# Sensors.net
KiCad netlist of a schematic drawn in Altium Designer
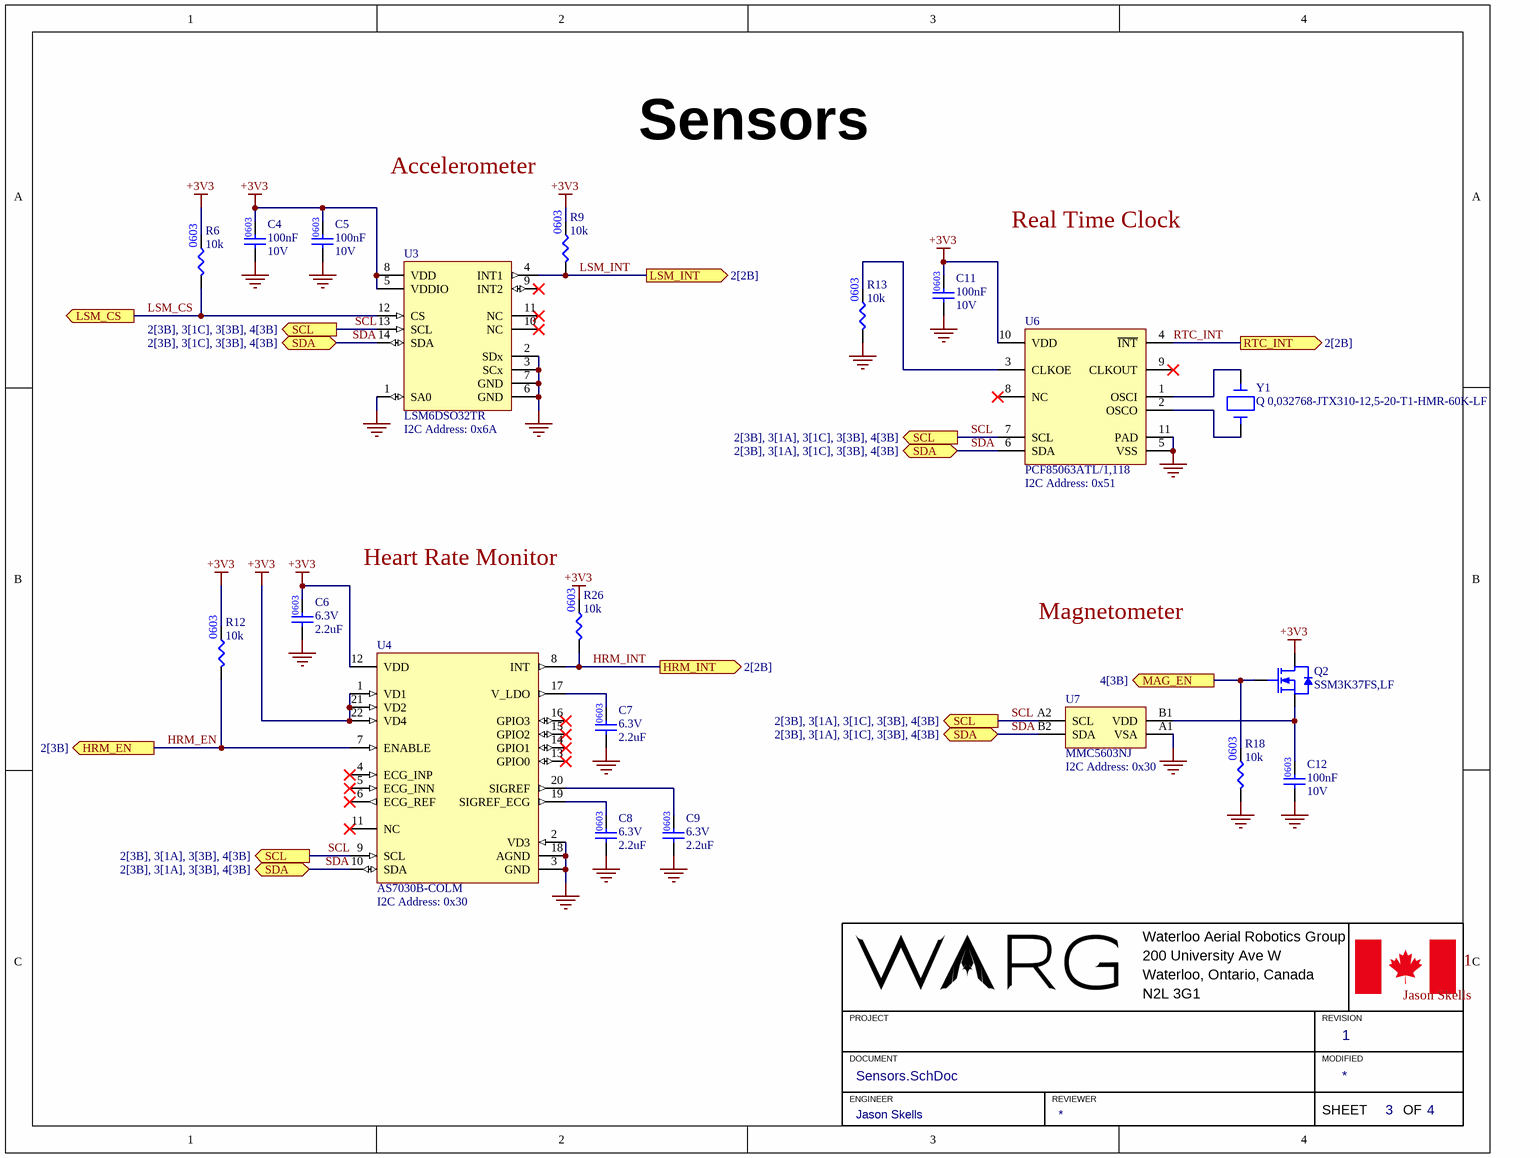
[diagram p0: Sensors.SchDoc]

(export (version "E")
  (design (tool "Eeschema 10.0.6"))
  (components
    (comp (ref "C4")
      (value "CC0603KRX7R6BB104")
      (footprint "CAP_0603")
      (description "CAP CER 0.1UF 10V X7R 0603")
      (fields
        (field (name "MANUFACTURER") "Yageo")
        (field (name "TOLERANCE") "10%")
        (field (name "CAPACITANCE") "100nF")
        (field (name "VOLTAGE RATING") "10V")
      )
      (libsource (lib "Smartwatch_Lib") (part "CC0603KRX7R6BB104"))
    )
    (comp (ref "C5")
      (value "CC0603KRX7R6BB104")
      (footprint "CAP_0603")
      (description "CAP CER 0.1UF 10V X7R 0603")
      (fields
        (field (name "MANUFACTURER") "Yageo")
        (field (name "TOLERANCE") "10%")
        (field (name "CAPACITANCE") "100nF")
        (field (name "VOLTAGE RATING") "10V")
      )
      (libsource (lib "Smartwatch_Lib") (part "CC0603KRX7R6BB104"))
    )
    (comp (ref "C6")
      (value "CL10A225KQ8NNNC")
      (footprint "CAP_0603")
      (description "CAP CER 2.2UF 6.3V X5R 0603")
      (fields
        (field (name "MANUFACTURER") "Samsung")
        (field (name "TOLERANCE") "10%")
        (field (name "VOLTAGE RATING") "6.3V")
        (field (name "CAPACITANCE") "2.2uF")
      )
      (libsource (lib "Smartwatch_Lib") (part "CL10A225KQ8NNNC"))
    )
    (comp (ref "C7")
      (value "CL10A225KQ8NNNC")
      (footprint "CAP_0603")
      (description "CAP CER 2.2UF 6.3V X5R 0603")
      (fields
        (field (name "MANUFACTURER") "Samsung")
        (field (name "TOLERANCE") "10%")
        (field (name "VOLTAGE RATING") "6.3V")
        (field (name "CAPACITANCE") "2.2uF")
      )
      (libsource (lib "Smartwatch_Lib") (part "CL10A225KQ8NNNC"))
    )
    (comp (ref "C8")
      (value "CL10A225KQ8NNNC")
      (footprint "CAP_0603")
      (description "CAP CER 2.2UF 6.3V X5R 0603")
      (fields
        (field (name "MANUFACTURER") "Samsung")
        (field (name "TOLERANCE") "10%")
        (field (name "VOLTAGE RATING") "6.3V")
        (field (name "CAPACITANCE") "2.2uF")
      )
      (libsource (lib "Smartwatch_Lib") (part "CL10A225KQ8NNNC"))
    )
    (comp (ref "C9")
      (value "CL10A225KQ8NNNC")
      (footprint "CAP_0603")
      (description "CAP CER 2.2UF 6.3V X5R 0603")
      (fields
        (field (name "MANUFACTURER") "Samsung")
        (field (name "TOLERANCE") "10%")
        (field (name "VOLTAGE RATING") "6.3V")
        (field (name "CAPACITANCE") "2.2uF")
      )
      (libsource (lib "Smartwatch_Lib") (part "CL10A225KQ8NNNC"))
    )
    (comp (ref "C11")
      (value "CC0603KRX7R6BB104")
      (footprint "CAP_0603")
      (description "CAP CER 0.1UF 10V X7R 0603")
      (fields
        (field (name "MANUFACTURER") "Yageo")
        (field (name "TOLERANCE") "10%")
        (field (name "CAPACITANCE") "100nF")
        (field (name "VOLTAGE RATING") "10V")
      )
      (libsource (lib "Smartwatch_Lib") (part "CC0603KRX7R6BB104"))
    )
    (comp (ref "C12")
      (value "CC0603KRX7R6BB104")
      (footprint "CAP_0603")
      (description "CAP CER 0.1UF 10V X7R 0603")
      (fields
        (field (name "MANUFACTURER") "Yageo")
        (field (name "TOLERANCE") "10%")
        (field (name "CAPACITANCE") "100nF")
        (field (name "VOLTAGE RATING") "10V")
      )
      (libsource (lib "Smartwatch_Lib") (part "CC0603KRX7R6BB104"))
    )
    (comp (ref "Q2")
      (value "SSM3K37FS,LF")
      (footprint "SSM3K37FS,LF")
      (description "MOSFET NCH 20V 200MA SSM")
      (fields
        (field (name "MANUFACTURER") "Toshiba")
        (field (name "MANUFACTURER PART NUMBER") "SSM3K37FS,LF")
      )
      (libsource (lib "Smartwatch_Lib") (part "SSM3K37FS,LF"))
    )
    (comp (ref "R6")
      (value "RNCP0603FTD10K0")
      (footprint "RES_0603")
      (description "Res Thin Film 0603 10K Ohm 1% 1/8W ±100ppm/°C Molded SMD SMD Paper T/R")
      (fields
        (field (name "MANUFACTURER") "Stackpole Electronics")
        (field (name "TOLERANCE") "1%")
        (field (name "RESISTANCE") "10k")
      )
      (libsource (lib "Smartwatch_Lib") (part "RNCP0603FTD10K0"))
    )
    (comp (ref "R9")
      (value "RNCP0603FTD10K0")
      (footprint "RES_0603")
      (description "Res Thin Film 0603 10K Ohm 1% 1/8W ±100ppm/°C Molded SMD SMD Paper T/R")
      (fields
        (field (name "MANUFACTURER") "Stackpole Electronics")
        (field (name "TOLERANCE") "1%")
        (field (name "RESISTANCE") "10k")
      )
      (libsource (lib "Smartwatch_Lib") (part "RNCP0603FTD10K0"))
    )
    (comp (ref "R12")
      (value "RNCP0603FTD10K0")
      (footprint "RES_0603")
      (description "Res Thin Film 0603 10K Ohm 1% 1/8W ±100ppm/°C Molded SMD SMD Paper T/R")
      (fields
        (field (name "MANUFACTURER") "Stackpole Electronics")
        (field (name "TOLERANCE") "1%")
        (field (name "RESISTANCE") "10k")
      )
      (libsource (lib "Smartwatch_Lib") (part "RNCP0603FTD10K0"))
    )
    (comp (ref "R13")
      (value "RNCP0603FTD10K0")
      (footprint "RES_0603")
      (description "Res Thin Film 0603 10K Ohm 1% 1/8W ±100ppm/°C Molded SMD SMD Paper T/R")
      (fields
        (field (name "MANUFACTURER") "Stackpole Electronics")
        (field (name "TOLERANCE") "1%")
        (field (name "RESISTANCE") "10k")
      )
      (libsource (lib "Smartwatch_Lib") (part "RNCP0603FTD10K0"))
    )
    (comp (ref "R18")
      (value "RNCP0603FTD10K0")
      (footprint "RES_0603")
      (description "Res Thin Film 0603 10K Ohm 1% 1/8W ±100ppm/°C Molded SMD SMD Paper T/R")
      (fields
        (field (name "MANUFACTURER") "Stackpole Electronics")
        (field (name "TOLERANCE") "1%")
        (field (name "RESISTANCE") "10k")
      )
      (libsource (lib "Smartwatch_Lib") (part "RNCP0603FTD10K0"))
    )
    (comp (ref "R26")
      (value "RNCP0603FTD10K0")
      (footprint "RES_0603")
      (description "Res Thin Film 0603 10K Ohm 1% 1/8W ±100ppm/°C Molded SMD SMD Paper T/R")
      (fields
        (field (name "MANUFACTURER") "Stackpole Electronics")
        (field (name "TOLERANCE") "1%")
        (field (name "RESISTANCE") "10k")
      )
      (libsource (lib "Smartwatch_Lib") (part "RNCP0603FTD10K0"))
    )
    (comp (ref "U3")
      (value "LSM6DSO32TR")
      (footprint "LSM6DSO32")
      (description "Accelerometer and 3D Gyroscope 3D Always-On 1.71V to 3.6V 0.55mA 14-Pin LGA T/R")
      (fields (field (name "MANUFACTURER") "STMicroelectronics"))
      (libsource (lib "Smartwatch_Lib") (part "LSM6DSO32TR"))
    )
    (comp (ref "U4")
      (value "AS7030B-COLM")
      (footprint "AS7030B-COLM")
      (description "AS703x Series 5.5 V Medical or Consumer Grade Vital Sign Sensor Module - OLGA-22")
      (fields (field (name "MANUFACTURER") "ams"))
      (libsource (lib "Smartwatch_Lib") (part "AS7030B-COLM"))
    )
    (comp (ref "U6")
      (value "PCF85063ATL/1,118")
      (footprint "PCF85063ATL/1,118")
      (description "IC RTC CLK/CALENDAR I2C 10-SON")
      (fields (field (name "MANUFACTURER") "NXP Semiconductors"))
      (libsource (lib "Smartwatch_Lib") (part "PCF85063ATL/1,118"))
    )
    (comp (ref "U7")
      (value "MMC5603NJ")
      (footprint "MMC5603NJ")
      (description "3-AXIS Amr Magnetic Sensor")
      (fields (field (name "MANUFACTURER") "Memsic") (field (name "MANUFACTURER PART NUMBER") "MMC5603NJ"))
      (libsource (lib "Smartwatch_Lib") (part "MMC5603NJ"))
    )
    (comp (ref "Y1")
      (value "Q 0,032768-JTX310-12,5-20-T1-HMR-60K-LF")
      (footprint "Q 0,032768-JTX310-12,5-20-T1-HMR-60K-LF")
      (description "Crystal 32.7680KHZ 12.5PF SMD")
      (fields
        (field (name "MANUFACTURER") "Jauch")
        (field (name "MANUFACTURER PART NUMBER") "Q 0,032768-JTX310-12,5-20-T1-HMR-60K-LF")
      )
      (libsource (lib "Smartwatch_Lib") (part "Q 0,032768-JTX310-12,5-20-T1-HMR-60K-LF"))
    )
  )
  (nets
    (net (code "1") (name "+3V3") (class "Default")
      (node (ref "C11") (pin "2") (pinfunction "2_2") (pintype "passive"))
      (node (ref "C4") (pin "2") (pinfunction "2_2") (pintype "passive"))
      (node (ref "C5") (pin "2") (pinfunction "2_2") (pintype "passive"))
      (node (ref "C6") (pin "2") (pinfunction "2_2") (pintype "passive"))
      (node (ref "Q2") (pin "1") (pinfunction "Drain_1") (pintype "passive"))
      (node (ref "R12") (pin "2") (pinfunction "2_2") (pintype "passive"))
      (node (ref "R26") (pin "2") (pinfunction "2_2") (pintype "passive"))
      (node (ref "R6") (pin "2") (pinfunction "2_2") (pintype "passive"))
      (node (ref "R9") (pin "2") (pinfunction "2_2") (pintype "passive"))
      (node (ref "U3") (pin "5") (pinfunction "VDDIO_5") (pintype "power_in"))
      (node (ref "U3") (pin "8") (pinfunction "VDD_8") (pintype "power_in"))
      (node (ref "U4") (pin "1") (pinfunction "VD1_1") (pintype "input"))
      (node (ref "U4") (pin "12") (pinfunction "VDD_12") (pintype "power_in"))
      (node (ref "U4") (pin "21") (pinfunction "VD2_21") (pintype "input"))
      (node (ref "U4") (pin "22") (pinfunction "VD4_22") (pintype "input"))
      (node (ref "U6") (pin "10") (pinfunction "VDD_10") (pintype "passive"))
    )
    (net (code "2") (name "/HRM_EN") (class "Default")
      (node (ref "R12") (pin "1") (pinfunction "1_1") (pintype "passive"))
      (node (ref "U4") (pin "7") (pinfunction "ENABLE_7") (pintype "input"))
    )
    (net (code "3") (name "/HRM_INT") (class "Default")
      (node (ref "R26") (pin "1") (pinfunction "1_1") (pintype "passive"))
      (node (ref "U4") (pin "8") (pinfunction "INT_8") (pintype "output"))
    )
    (net (code "4") (name "/LSM_CS") (class "Default")
      (node (ref "R6") (pin "1") (pinfunction "1_1") (pintype "passive"))
      (node (ref "U3") (pin "12") (pinfunction "CS_12") (pintype "input"))
    )
    (net (code "5") (name "/LSM_INT") (class "Default")
      (node (ref "R9") (pin "1") (pinfunction "1_1") (pintype "passive"))
      (node (ref "U3") (pin "4") (pinfunction "INT1_4") (pintype "output"))
    )
    (net (code "6") (name "/MAG_EN") (class "Default")
      (node (ref "Q2") (pin "2") (pinfunction "Gate_2") (pintype "passive"))
      (node (ref "R18") (pin "2") (pinfunction "2_2") (pintype "passive"))
    )
    (net (code "7") (name "/RTC_INT") (class "Default")
      (node (ref "U6") (pin "4") (pinfunction "~{INT}_4") (pintype "passive"))
    )
    (net (code "8") (name "/SCL") (class "Default")
      (node (ref "U3") (pin "13") (pinfunction "SCL_13") (pintype "input"))
      (node (ref "U4") (pin "9") (pinfunction "SCL_9") (pintype "input"))
      (node (ref "U6") (pin "7") (pinfunction "SCL_7") (pintype "passive"))
      (node (ref "U7") (pin "A2") (pinfunction "SCL_A2") (pintype "passive"))
    )
    (net (code "9") (name "/SDA") (class "Default")
      (node (ref "U3") (pin "14") (pinfunction "SDA_14") (pintype "bidirectional"))
      (node (ref "U4") (pin "10") (pinfunction "SDA_10") (pintype "bidirectional"))
      (node (ref "U6") (pin "6") (pinfunction "SDA_6") (pintype "passive"))
      (node (ref "U7") (pin "B2") (pinfunction "SDA_B2") (pintype "passive"))
    )
    (net (code "10") (name "GND") (class "Default")
      (node (ref "C11") (pin "1") (pinfunction "1_1") (pintype "passive"))
      (node (ref "C12") (pin "1") (pinfunction "1_1") (pintype "passive"))
      (node (ref "C4") (pin "1") (pinfunction "1_1") (pintype "passive"))
      (node (ref "C5") (pin "1") (pinfunction "1_1") (pintype "passive"))
      (node (ref "C6") (pin "1") (pinfunction "1_1") (pintype "passive"))
      (node (ref "C7") (pin "1") (pinfunction "1_1") (pintype "passive"))
      (node (ref "C8") (pin "1") (pinfunction "1_1") (pintype "passive"))
      (node (ref "C9") (pin "1") (pinfunction "1_1") (pintype "passive"))
      (node (ref "R13") (pin "1") (pinfunction "1_1") (pintype "passive"))
      (node (ref "R18") (pin "1") (pinfunction "1_1") (pintype "passive"))
      (node (ref "U3") (pin "1") (pinfunction "SA0_1") (pintype "bidirectional"))
      (node (ref "U3") (pin "2") (pinfunction "SDx_2") (pintype "passive"))
      (node (ref "U3") (pin "3") (pinfunction "SCx_3") (pintype "passive"))
      (node (ref "U3") (pin "6") (pinfunction "GND_6") (pintype "power_in"))
      (node (ref "U3") (pin "7") (pinfunction "GND_7") (pintype "power_in"))
      (node (ref "U4") (pin "18") (pinfunction "AGND_18") (pintype "power_in"))
      (node (ref "U4") (pin "2") (pinfunction "VD3_2") (pintype "input"))
      (node (ref "U4") (pin "3") (pinfunction "GND_3") (pintype "power_in"))
      (node (ref "U6") (pin "11") (pinfunction "PAD_11") (pintype "passive"))
      (node (ref "U6") (pin "5") (pinfunction "VSS_5") (pintype "passive"))
      (node (ref "U7") (pin "A1") (pinfunction "VSA_A1") (pintype "passive"))
    )
    (net (code "11") (name "Net-(Q2-Source)") (class "Default")
      (node (ref "C12") (pin "2") (pinfunction "2_2") (pintype "passive"))
      (node (ref "Q2") (pin "3") (pinfunction "Source_3") (pintype "passive"))
      (node (ref "U7") (pin "B1") (pinfunction "VDD_B1") (pintype "passive"))
    )
    (net (code "12") (name "Net-(U4-SIGREF)") (class "Default")
      (node (ref "C9") (pin "2") (pinfunction "2_2") (pintype "passive"))
      (node (ref "U4") (pin "20") (pinfunction "SIGREF_20") (pintype "output"))
    )
    (net (code "13") (name "Net-(U4-SIGREF_ECG)") (class "Default")
      (node (ref "C8") (pin "2") (pinfunction "2_2") (pintype "passive"))
      (node (ref "U4") (pin "19") (pinfunction "SIGREF_ECG_19") (pintype "output"))
    )
    (net (code "14") (name "Net-(U4-V_LDO)") (class "Default")
      (node (ref "C7") (pin "2") (pinfunction "2_2") (pintype "passive"))
      (node (ref "U4") (pin "17") (pinfunction "V_LDO_17") (pintype "output"))
    )
    (net (code "15") (name "Net-(U6-CLKOE)") (class "Default")
      (node (ref "R13") (pin "2") (pinfunction "2_2") (pintype "passive"))
      (node (ref "U6") (pin "3") (pinfunction "CLKOE_3") (pintype "passive"))
    )
    (net (code "16") (name "Net-(U6-OSCI)") (class "Default")
      (node (ref "U6") (pin "1") (pinfunction "OSCI_1") (pintype "passive"))
      (node (ref "Y1") (pin "1") (pinfunction "In/Out_1") (pintype "passive"))
    )
    (net (code "17") (name "Net-(U6-OSCO)") (class "Default")
      (node (ref "U6") (pin "2") (pinfunction "OSCO_2") (pintype "passive"))
      (node (ref "Y1") (pin "2") (pinfunction "Out/In_2") (pintype "passive"))
    )
    (net (code "18") (name "unconnected-(U3-INT2-Pad9)") (class "Default")
      (node (ref "U3") (pin "9") (pinfunction "INT2_9") (pintype "bidirectional+no_connect"))
    )
    (net (code "19") (name "unconnected-(U3-NC-Pad10)") (class "Default")
      (node (ref "U3") (pin "10") (pinfunction "NC_10") (pintype "passive+no_connect"))
    )
    (net (code "20") (name "unconnected-(U3-NC-Pad11)") (class "Default")
      (node (ref "U3") (pin "11") (pinfunction "NC_11") (pintype "passive+no_connect"))
    )
    (net (code "21") (name "unconnected-(U4-ECG_INN-Pad5)") (class "Default")
      (node (ref "U4") (pin "5") (pinfunction "ECG_INN_5") (pintype "input+no_connect"))
    )
    (net (code "22") (name "unconnected-(U4-ECG_INP-Pad4)") (class "Default")
      (node (ref "U4") (pin "4") (pinfunction "ECG_INP_4") (pintype "input+no_connect"))
    )
    (net (code "23") (name "unconnected-(U4-ECG_REF-Pad6)") (class "Default")
      (node (ref "U4") (pin "6") (pinfunction "ECG_REF_6") (pintype "output+no_connect"))
    )
    (net (code "24") (name "unconnected-(U4-GPIO0-Pad13)") (class "Default")
      (node (ref "U4") (pin "13") (pinfunction "GPIO0_13") (pintype "bidirectional+no_connect"))
    )
    (net (code "25") (name "unconnected-(U4-GPIO1-Pad14)") (class "Default")
      (node (ref "U4") (pin "14") (pinfunction "GPIO1_14") (pintype "bidirectional+no_connect"))
    )
    (net (code "26") (name "unconnected-(U4-GPIO2-Pad15)") (class "Default")
      (node (ref "U4") (pin "15") (pinfunction "GPIO2_15") (pintype "bidirectional+no_connect"))
    )
    (net (code "27") (name "unconnected-(U4-GPIO3-Pad16)") (class "Default")
      (node (ref "U4") (pin "16") (pinfunction "GPIO3_16") (pintype "bidirectional+no_connect"))
    )
    (net (code "28") (name "unconnected-(U4-NC-Pad11)") (class "Default")
      (node (ref "U4") (pin "11") (pinfunction "NC_11") (pintype "passive+no_connect"))
    )
    (net (code "29") (name "unconnected-(U6-CLKOUT-Pad9)") (class "Default")
      (node (ref "U6") (pin "9") (pinfunction "CLKOUT_9") (pintype "passive+no_connect"))
    )
    (net (code "30") (name "unconnected-(U6-NC-Pad8)") (class "Default")
      (node (ref "U6") (pin "8") (pinfunction "NC_8") (pintype "passive+no_connect"))
    )
  )
)
